# conf.net
KiCad netlist of a schematic drawn in Altium Designer
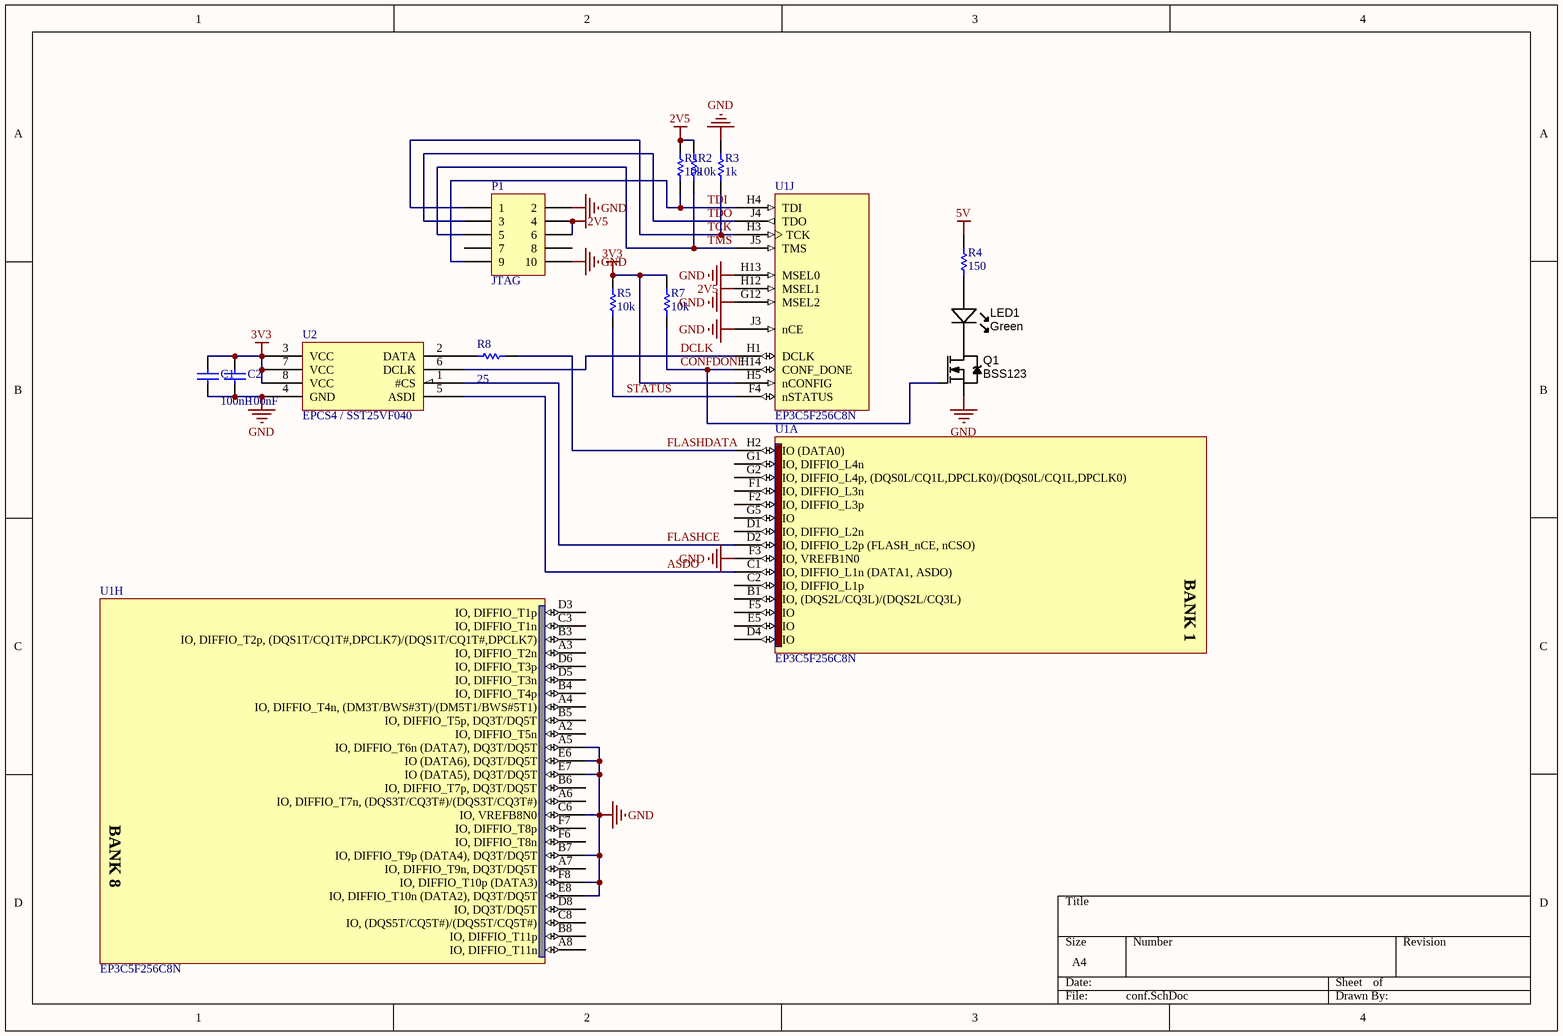
[diagram p0: conf.SchDoc]

(export (version "E")
  (design (tool "Eeschema 10.0.6"))
  (components
    (comp (ref "C1")
      (value "100nF")
      (footprint "CAPC1005X06L")
      (description "Capacitor")
      (fields (field (name "PUBLISHER") "Altium Limited"))
      (libsource (lib "Miscellaneous Devices") (part "Cap"))
    )
    (comp (ref "C2")
      (value "100nF")
      (footprint "CAPC1005X06L")
      (description "Capacitor")
      (fields (field (name "PUBLISHER") "Altium Limited"))
      (libsource (lib "Miscellaneous Devices") (part "Cap"))
    )
    (comp (ref "LED1")
      (value "Green")
      (footprint "LED-0603-GREEN")
      (description "LED 0603 SMD Green 570nm 50mcd 20mA")
      (libsource (lib "PBL - Light Sources") (part "LED_SMD_Green_0603_570nm"))
    )
    (comp (ref "P1")
      (value "JTAG")
      (footprint "HDR2X5")
      (description "Header, 5-Pin, Dual row")
      (fields (field (name "PUBLISHER") "Altium Limited"))
      (libsource (lib "Miscellaneous Connectors") (part "Header 5X2"))
    )
    (comp (ref "Q1")
      (value "BSS123")
      (footprint "SOT23-3")
      (description "MOSFET SMD N-CH 100V 170mA SOT23-3")
      (libsource (lib "PBL - Transistors") (part "MOSFET_BSS123"))
    )
    (comp (ref "R1")
      (value "10k")
      (footprint "RESC2012X70N")
      (description "Resistor")
      (fields (field (name "Comment") "Res1") (field (name "PUBLISHER") "Altium Limited"))
      (libsource (lib "Miscellaneous Devices") (part "Res1"))
    )
    (comp (ref "R2")
      (value "10k")
      (footprint "RESC2012X70N")
      (description "Resistor")
      (fields (field (name "Comment") "Res1") (field (name "PUBLISHER") "Altium Limited"))
      (libsource (lib "Miscellaneous Devices") (part "Res1"))
    )
    (comp (ref "R3")
      (value "1k")
      (footprint "RESC2012X70N")
      (description "Resistor")
      (fields (field (name "Comment") "Res1") (field (name "PUBLISHER") "Altium Limited"))
      (libsource (lib "Miscellaneous Devices") (part "Res1"))
    )
    (comp (ref "R4")
      (value "150")
      (footprint "RESC2012X70N")
      (description "Resistor")
      (fields (field (name "Comment") "Res1") (field (name "PUBLISHER") "Altium Limited"))
      (libsource (lib "Miscellaneous Devices") (part "Res1"))
    )
    (comp (ref "R5")
      (value "10k")
      (footprint "RESC2012X70N")
      (description "Resistor")
      (fields (field (name "Comment") "Res1") (field (name "PUBLISHER") "Altium Limited"))
      (libsource (lib "Miscellaneous Devices") (part "Res1"))
    )
    (comp (ref "R7")
      (value "10k")
      (footprint "RESC2012X70N")
      (description "Resistor")
      (fields (field (name "Comment") "Res1") (field (name "PUBLISHER") "Altium Limited"))
      (libsource (lib "Miscellaneous Devices") (part "Res1"))
    )
    (comp (ref "R8")
      (value "25")
      (footprint "RESC2012X70N")
      (description "Resistor")
      (fields (field (name "Comment") "Res1") (field (name "PUBLISHER") "Altium Limited"))
      (libsource (lib "Miscellaneous Devices") (part "Res1"))
    )
    (comp (ref "U1")
      (value "EP3C5F256C8N")
      (footprint "FBGA256-2")
      (fields (field (name "PUBLISHER") "Altium Limited"))
      (libsource (lib "") (part "EP3C5F256C8N_1"))
    )
    (comp (ref "U2")
      (value "EPCS4 / SST25VF040")
      (footprint "SOIC127P600X175-8AN")
      (libsource (lib "parts") (part "EPCS4"))
    )
  )
  (nets
    (net (code "1") (name "/ASDO") (class "Default")
      (node (ref "U1") (pin "C1") (pinfunction "IO,_DIFFIO_L1n_(DATA1,_ASDO)_C1") (pintype "bidirectional"))
      (node (ref "U2") (pin "5") (pinfunction "ASDI_5") (pintype "passive"))
    )
    (net (code "2") (name "/CONFDONE") (class "Default")
      (node (ref "Q1") (pin "1") (pinfunction "G_1") (pintype "passive"))
      (node (ref "R7") (pin "1") (pinfunction "1_1") (pintype "passive"))
      (node (ref "U1") (pin "H14") (pinfunction "CONF_DONE_H14") (pintype "bidirectional"))
    )
    (net (code "3") (name "/DCLK") (class "Default")
      (node (ref "U1") (pin "H1") (pinfunction "DCLK_H1") (pintype "bidirectional"))
      (node (ref "U2") (pin "6") (pinfunction "DCLK_6") (pintype "passive"))
    )
    (net (code "4") (name "/FLASHCE") (class "Default")
      (node (ref "U1") (pin "D2") (pinfunction "IO,_DIFFIO_L2p_(FLASH_nCE,_nCSO)_D2") (pintype "bidirectional"))
      (node (ref "U2") (pin "1") (pinfunction "#CS_1") (pintype "passive"))
    )
    (net (code "5") (name "/FLASHDATA") (class "Default")
      (node (ref "R8") (pin "2") (pinfunction "2_2") (pintype "passive"))
      (node (ref "U1") (pin "H2") (pinfunction "IO_(DATA0)_H2") (pintype "bidirectional"))
    )
    (net (code "6") (name "/STATUS") (class "Default")
      (node (ref "R5") (pin "1") (pinfunction "1_1") (pintype "passive"))
      (node (ref "U1") (pin "F4") (pinfunction "nSTATUS_F4") (pintype "bidirectional"))
    )
    (net (code "7") (name "/TCK") (class "Default")
      (node (ref "P1") (pin "1") (pinfunction "1_1") (pintype "passive"))
      (node (ref "R3") (pin "1") (pinfunction "1_1") (pintype "passive"))
      (node (ref "U1") (pin "H3") (pinfunction "TCK_H3") (pintype "input"))
    )
    (net (code "8") (name "/TDI") (class "Default")
      (node (ref "P1") (pin "9") (pinfunction "9_9") (pintype "passive"))
      (node (ref "R1") (pin "1") (pinfunction "1_1") (pintype "passive"))
      (node (ref "U1") (pin "H4") (pinfunction "TDI_H4") (pintype "input"))
    )
    (net (code "9") (name "/TDO") (class "Default")
      (node (ref "P1") (pin "3") (pinfunction "3_3") (pintype "passive"))
      (node (ref "U1") (pin "J4") (pinfunction "TDO_J4") (pintype "output"))
    )
    (net (code "10") (name "/TMS") (class "Default")
      (node (ref "P1") (pin "5") (pinfunction "5_5") (pintype "passive"))
      (node (ref "R2") (pin "1") (pinfunction "1_1") (pintype "passive"))
      (node (ref "U1") (pin "J5") (pinfunction "TMS_J5") (pintype "input"))
    )
    (net (code "11") (name "2V5") (class "Default")
      (node (ref "P1") (pin "4") (pinfunction "4_4") (pintype "passive"))
      (node (ref "P1") (pin "6") (pinfunction "6_6") (pintype "passive"))
      (node (ref "R1") (pin "2") (pinfunction "2_2") (pintype "passive"))
      (node (ref "R2") (pin "2") (pinfunction "2_2") (pintype "passive"))
      (node (ref "U1") (pin "H12") (pinfunction "MSEL1_H12") (pintype "input"))
    )
    (net (code "12") (name "3V3") (class "Default")
      (node (ref "C1") (pin "2") (pinfunction "2_2") (pintype "passive"))
      (node (ref "C2") (pin "2") (pinfunction "2_2") (pintype "passive"))
      (node (ref "R5") (pin "2") (pinfunction "2_2") (pintype "passive"))
      (node (ref "R7") (pin "2") (pinfunction "2_2") (pintype "passive"))
      (node (ref "U1") (pin "H5") (pinfunction "nCONFIG_H5") (pintype "input"))
      (node (ref "U2") (pin "3") (pinfunction "VCC_3") (pintype "passive"))
      (node (ref "U2") (pin "7") (pinfunction "VCC_7") (pintype "passive"))
      (node (ref "U2") (pin "8") (pinfunction "VCC_8") (pintype "passive"))
    )
    (net (code "13") (name "5V") (class "Default")
      (node (ref "R4") (pin "2") (pinfunction "2_2") (pintype "passive"))
    )
    (net (code "14") (name "GND") (class "Default")
      (node (ref "C1") (pin "1") (pinfunction "1_1") (pintype "passive"))
      (node (ref "C2") (pin "1") (pinfunction "1_1") (pintype "passive"))
      (node (ref "P1") (pin "10") (pinfunction "10_10") (pintype "passive"))
      (node (ref "P1") (pin "2") (pinfunction "2_2") (pintype "passive"))
      (node (ref "Q1") (pin "2") (pinfunction "S_2") (pintype "passive"))
      (node (ref "R3") (pin "2") (pinfunction "2_2") (pintype "passive"))
      (node (ref "U1") (pin "A5") (pinfunction "IO,_DIFFIO_T6n_(DATA7),_DQ3T/DQ5T_A5") (pintype "bidirectional"))
      (node (ref "U1") (pin "B7") (pinfunction "IO,_DIFFIO_T9p_(DATA4),_DQ3T/DQ5T_B7") (pintype "bidirectional"))
      (node (ref "U1") (pin "C6") (pinfunction "IO,_VREFB8N0_C6") (pintype "bidirectional"))
      (node (ref "U1") (pin "E6") (pinfunction "IO_(DATA6),_DQ3T/DQ5T_E6") (pintype "bidirectional"))
      (node (ref "U1") (pin "E7") (pinfunction "IO_(DATA5),_DQ3T/DQ5T_E7") (pintype "bidirectional"))
      (node (ref "U1") (pin "E8") (pinfunction "IO,_DIFFIO_T10n_(DATA2),_DQ3T/DQ5T_E8") (pintype "bidirectional"))
      (node (ref "U1") (pin "F3") (pinfunction "IO,_VREFB1N0_F3") (pintype "bidirectional"))
      (node (ref "U1") (pin "F8") (pinfunction "IO,_DIFFIO_T10p_(DATA3)_F8") (pintype "bidirectional"))
      (node (ref "U1") (pin "G12") (pinfunction "MSEL2_G12") (pintype "input"))
      (node (ref "U1") (pin "H13") (pinfunction "MSEL0_H13") (pintype "input"))
      (node (ref "U1") (pin "J3") (pinfunction "nCE_J3") (pintype "input"))
      (node (ref "U2") (pin "4") (pinfunction "GND_4") (pintype "passive"))
    )
    (net (code "15") (name "Net-(LED1-PadA)") (class "Default")
      (node (ref "LED1") (pin "A") (pinfunction "A_A") (pintype "passive"))
      (node (ref "R4") (pin "1") (pinfunction "1_1") (pintype "passive"))
    )
    (net (code "16") (name "Net-(Q1-D)") (class "Default")
      (node (ref "LED1") (pin "K") (pinfunction "K_K") (pintype "passive"))
      (node (ref "Q1") (pin "3") (pinfunction "D_3") (pintype "passive"))
    )
    (net (code "17") (name "Net-(U2-DATA)") (class "Default")
      (node (ref "R8") (pin "1") (pinfunction "1_1") (pintype "passive"))
      (node (ref "U2") (pin "2") (pinfunction "DATA_2") (pintype "passive"))
    )
    (net (code "18") (name "unconnected-(P1-Pad7)") (class "Default")
      (node (ref "P1") (pin "7") (pinfunction "7_7") (pintype "passive"))
    )
    (net (code "19") (name "unconnected-(P1-Pad8)") (class "Default")
      (node (ref "P1") (pin "8") (pinfunction "8_8") (pintype "passive"))
    )
    (net (code "20") (name "unconnected-(U1A-IO,_(DQS2L{slash}CQ3L){slash}(DQS2L{slash}CQ3L)-PadB1)") (class "Default")
      (node (ref "U1") (pin "B1") (pinfunction "IO,_(DQS2L/CQ3L)/(DQS2L/CQ3L)_B1") (pintype "bidirectional"))
    )
    (net (code "21") (name "unconnected-(U1A-IO,_DIFFIO_L1p-PadC2)") (class "Default")
      (node (ref "U1") (pin "C2") (pinfunction "IO,_DIFFIO_L1p_C2") (pintype "bidirectional"))
    )
    (net (code "22") (name "unconnected-(U1A-IO,_DIFFIO_L2n-PadD1)") (class "Default")
      (node (ref "U1") (pin "D1") (pinfunction "IO,_DIFFIO_L2n_D1") (pintype "bidirectional"))
    )
    (net (code "23") (name "unconnected-(U1A-IO,_DIFFIO_L3n-PadF1)") (class "Default")
      (node (ref "U1") (pin "F1") (pinfunction "IO,_DIFFIO_L3n_F1") (pintype "bidirectional"))
    )
    (net (code "24") (name "unconnected-(U1A-IO,_DIFFIO_L3p-PadF2)") (class "Default")
      (node (ref "U1") (pin "F2") (pinfunction "IO,_DIFFIO_L3p_F2") (pintype "bidirectional"))
    )
    (net (code "25") (name "unconnected-(U1A-IO,_DIFFIO_L4n-PadG1)") (class "Default")
      (node (ref "U1") (pin "G1") (pinfunction "IO,_DIFFIO_L4n_G1") (pintype "bidirectional"))
    )
    (net (code "26") (name "unconnected-(U1A-IO,_DIFFIO_L4p,_(DQS0L{slash}CQ1L,DPCLK0){slash}(DQS0L{slash}CQ1L,DPCLK0)-PadG2)") (class "Default")
      (node (ref "U1") (pin "G2") (pinfunction "IO,_DIFFIO_L4p,_(DQS0L/CQ1L,DPCLK0)/(DQS0L/CQ1L,DPCLK0)_G2") (pintype "bidirectional"))
    )
    (net (code "27") (name "unconnected-(U1A-IO-PadD4)") (class "Default")
      (node (ref "U1") (pin "D4") (pinfunction "IO_D4") (pintype "bidirectional"))
    )
    (net (code "28") (name "unconnected-(U1A-IO-PadE5)") (class "Default")
      (node (ref "U1") (pin "E5") (pinfunction "IO_E5") (pintype "bidirectional"))
    )
    (net (code "29") (name "unconnected-(U1A-IO-PadF5)") (class "Default")
      (node (ref "U1") (pin "F5") (pinfunction "IO_F5") (pintype "bidirectional"))
    )
    (net (code "30") (name "unconnected-(U1A-IO-PadG5)") (class "Default")
      (node (ref "U1") (pin "G5") (pinfunction "IO_G5") (pintype "bidirectional"))
    )
    (net (code "31") (name "unconnected-(U1H-IO,_(DQS5T{slash}CQ5T#){slash}(DQS5T{slash}CQ5T#)-PadC8)") (class "Default")
      (node (ref "U1") (pin "C8") (pinfunction "IO,_(DQS5T/CQ5T#)/(DQS5T/CQ5T#)_C8") (pintype "bidirectional"))
    )
    (net (code "32") (name "unconnected-(U1H-IO,_DIFFIO_T1n-PadC3)") (class "Default")
      (node (ref "U1") (pin "C3") (pinfunction "IO,_DIFFIO_T1n_C3") (pintype "bidirectional"))
    )
    (net (code "33") (name "unconnected-(U1H-IO,_DIFFIO_T1p-PadD3)") (class "Default")
      (node (ref "U1") (pin "D3") (pinfunction "IO,_DIFFIO_T1p_D3") (pintype "bidirectional"))
    )
    (net (code "34") (name "unconnected-(U1H-IO,_DIFFIO_T2n-PadA3)") (class "Default")
      (node (ref "U1") (pin "A3") (pinfunction "IO,_DIFFIO_T2n_A3") (pintype "bidirectional"))
    )
    (net (code "35") (name "unconnected-(U1H-IO,_DIFFIO_T2p,_(DQS1T{slash}CQ1T#,DPCLK7){slash}(DQS1T{slash}CQ1T#,DPCLK7)-PadB3)") (class "Default")
      (node (ref "U1") (pin "B3") (pinfunction "IO,_DIFFIO_T2p,_(DQS1T/CQ1T#,DPCLK7)/(DQS1T/CQ1T#,DPCLK7)_B3") (pintype "bidirectional"))
    )
    (net (code "36") (name "unconnected-(U1H-IO,_DIFFIO_T3n-PadD5)") (class "Default")
      (node (ref "U1") (pin "D5") (pinfunction "IO,_DIFFIO_T3n_D5") (pintype "bidirectional"))
    )
    (net (code "37") (name "unconnected-(U1H-IO,_DIFFIO_T3p-PadD6)") (class "Default")
      (node (ref "U1") (pin "D6") (pinfunction "IO,_DIFFIO_T3p_D6") (pintype "bidirectional"))
    )
    (net (code "38") (name "unconnected-(U1H-IO,_DIFFIO_T4n,_(DM3T{slash}BWS#3T){slash}(DM5T1{slash}BWS#5T1)-PadA4)") (class "Default")
      (node (ref "U1") (pin "A4") (pinfunction "IO,_DIFFIO_T4n,_(DM3T/BWS#3T)/(DM5T1/BWS#5T1)_A4") (pintype "bidirectional"))
    )
    (net (code "39") (name "unconnected-(U1H-IO,_DIFFIO_T4p-PadB4)") (class "Default")
      (node (ref "U1") (pin "B4") (pinfunction "IO,_DIFFIO_T4p_B4") (pintype "bidirectional"))
    )
    (net (code "40") (name "unconnected-(U1H-IO,_DIFFIO_T5n-PadA2)") (class "Default")
      (node (ref "U1") (pin "A2") (pinfunction "IO,_DIFFIO_T5n_A2") (pintype "bidirectional"))
    )
    (net (code "41") (name "unconnected-(U1H-IO,_DIFFIO_T5p,_DQ3T{slash}DQ5T-PadB5)") (class "Default")
      (node (ref "U1") (pin "B5") (pinfunction "IO,_DIFFIO_T5p,_DQ3T/DQ5T_B5") (pintype "bidirectional"))
    )
    (net (code "42") (name "unconnected-(U1H-IO,_DIFFIO_T7n,_(DQS3T{slash}CQ3T#){slash}(DQS3T{slash}CQ3T#)-PadA6)") (class "Default")
      (node (ref "U1") (pin "A6") (pinfunction "IO,_DIFFIO_T7n,_(DQS3T/CQ3T#)/(DQS3T/CQ3T#)_A6") (pintype "bidirectional"))
    )
    (net (code "43") (name "unconnected-(U1H-IO,_DIFFIO_T7p,_DQ3T{slash}DQ5T-PadB6)") (class "Default")
      (node (ref "U1") (pin "B6") (pinfunction "IO,_DIFFIO_T7p,_DQ3T/DQ5T_B6") (pintype "bidirectional"))
    )
    (net (code "44") (name "unconnected-(U1H-IO,_DIFFIO_T8n-PadF6)") (class "Default")
      (node (ref "U1") (pin "F6") (pinfunction "IO,_DIFFIO_T8n_F6") (pintype "bidirectional"))
    )
    (net (code "45") (name "unconnected-(U1H-IO,_DIFFIO_T8p-PadF7)") (class "Default")
      (node (ref "U1") (pin "F7") (pinfunction "IO,_DIFFIO_T8p_F7") (pintype "bidirectional"))
    )
    (net (code "46") (name "unconnected-(U1H-IO,_DIFFIO_T9n,_DQ3T{slash}DQ5T-PadA7)") (class "Default")
      (node (ref "U1") (pin "A7") (pinfunction "IO,_DIFFIO_T9n,_DQ3T/DQ5T_A7") (pintype "bidirectional"))
    )
    (net (code "47") (name "unconnected-(U1H-IO,_DIFFIO_T11n-PadA8)") (class "Default")
      (node (ref "U1") (pin "A8") (pinfunction "IO,_DIFFIO_T11n_A8") (pintype "bidirectional"))
    )
    (net (code "48") (name "unconnected-(U1H-IO,_DIFFIO_T11p-PadB8)") (class "Default")
      (node (ref "U1") (pin "B8") (pinfunction "IO,_DIFFIO_T11p_B8") (pintype "bidirectional"))
    )
    (net (code "49") (name "unconnected-(U1H-IO,_DQ3T{slash}DQ5T-PadD8)") (class "Default")
      (node (ref "U1") (pin "D8") (pinfunction "IO,_DQ3T/DQ5T_D8") (pintype "bidirectional"))
    )
  )
)
